# design.net
KiCad netlist of a schematic drawn in Altium Designer
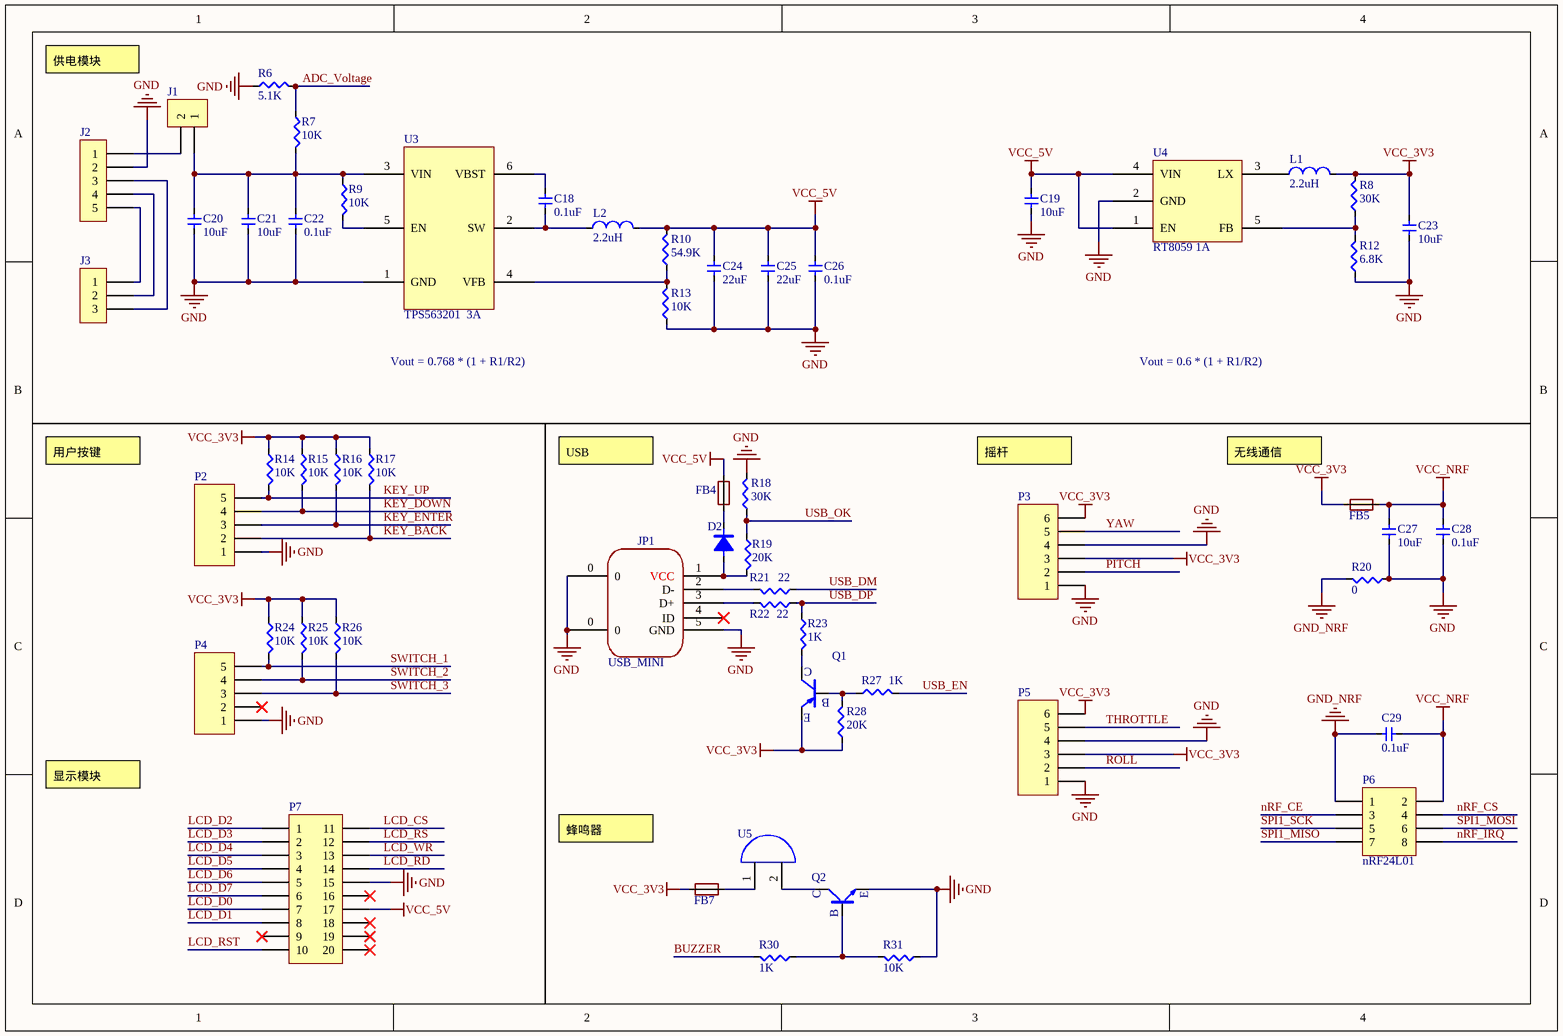
[diagram p0: 基本外设.SchDoc]

(export (version "E")
  (design (tool "Eeschema 10.0.6"))
  (components
    (comp (ref "C18")
      (value "0.1uF")
      (footprint "C 0603_L")
      (description "电容")
      (libsource (lib "SCHLIB") (part "CX_CAP"))
    )
    (comp (ref "C19")
      (value "10uF")
      (footprint "C 0603_L")
      (description "电容")
      (libsource (lib "SCHLIB") (part "CX_CAP"))
    )
    (comp (ref "C20")
      (value "10uF")
      (footprint "C 0603_L")
      (description "电容")
      (libsource (lib "SCHLIB") (part "CX_CAP"))
    )
    (comp (ref "C21")
      (value "10uF")
      (footprint "C 0603_L")
      (description "电容")
      (libsource (lib "SCHLIB") (part "CX_CAP"))
    )
    (comp (ref "C22")
      (value "0.1uF")
      (footprint "C 0603_L")
      (description "电容")
      (libsource (lib "SCHLIB") (part "CX_CAP"))
    )
    (comp (ref "C23")
      (value "10uF")
      (footprint "C 0603_L")
      (description "电容")
      (libsource (lib "SCHLIB") (part "CX_CAP"))
    )
    (comp (ref "C24")
      (value "22uF")
      (footprint "C 0603_L")
      (description "电容")
      (libsource (lib "SCHLIB") (part "CX_CAP"))
    )
    (comp (ref "C25")
      (value "22uF")
      (footprint "C 0603_L")
      (description "电容")
      (libsource (lib "SCHLIB") (part "CX_CAP"))
    )
    (comp (ref "C26")
      (value "0.1uF")
      (footprint "C 0603_L")
      (description "电容")
      (libsource (lib "SCHLIB") (part "CX_CAP"))
    )
    (comp (ref "C27")
      (value "10uF")
      (footprint "C 0603_L")
      (description "电容")
      (libsource (lib "SCHLIB") (part "CX_CAP"))
    )
    (comp (ref "C28")
      (value "0.1uF")
      (footprint "C 0603_L")
      (description "电容")
      (libsource (lib "SCHLIB") (part "CX_CAP"))
    )
    (comp (ref "C29")
      (value "0.1uF")
      (footprint "C 0603_L")
      (description "电容")
      (libsource (lib "SCHLIB") (part "CX_CAP"))
    )
    (comp (ref "D2")
      (value "DX_DIODE")
      (footprint "SMA")
      (description "普通二极管")
      (libsource (lib "MySCHLIB") (part "DX_DIODE"))
    )
    (comp (ref "FB4")
      (value "FB_BEAD")
      (footprint "FB 0603_L")
      (description "磁珠")
      (libsource (lib "MySCHLIB") (part "FB_BEAD"))
    )
    (comp (ref "FB5")
      (value "FB_BEAD")
      (footprint "FB 0603_L")
      (description "磁珠")
      (libsource (lib "") (part "FB_BEAD_1"))
    )
    (comp (ref "FB7")
      (value "FB_BEAD")
      (footprint "FB 0603_L")
      (description "磁珠")
      (libsource (lib "") (part "FB_BEAD_1"))
    )
    (comp (ref "J1")
      (value "PT_CON2")
      (footprint "PH2.0-WI-2P")
      (description "接插件")
      (libsource (lib "SCHLIB") (part "PT_CON2"))
    )
    (comp (ref "J2") (value "PT_CON5") (footprint "PH2.0-WI-5P") (libsource (lib "SCHLIB") (part "PT_CON5")))
    (comp (ref "J3") (value "~") (footprint "PH2.0-WI-3P") (libsource (lib "SCHLIB") (part "PT_CON3")))
    (comp (ref "JP1")
      (value "USB_MINI")
      (footprint "USB-MINI-5P-90度弯针")
      (libsource (lib "SCHLIB") (part "PT_USB_MINI"))
    )
    (comp (ref "L1")
      (value "2.2uH")
      (footprint "L 2520")
      (description "电感")
      (libsource (lib "SCHLIB") (part "LX_INDUCTOR_1"))
    )
    (comp (ref "L2")
      (value "2.2uH")
      (footprint "L 2520")
      (description "电感")
      (libsource (lib "SCHLIB") (part "LX_INDUCTOR_1"))
    )
    (comp (ref "P2")
      (value "Header 5")
      (footprint "XH1.25-WS-5P")
      (description "Header, 5-Pin")
      (fields (field (name "PUBLISHER") "Altium Limited"))
      (libsource (lib "Miscellaneous Connectors") (part "Header 5"))
    )
    (comp (ref "P3")
      (value "Header 6")
      (footprint "PH2.0-WS-6P")
      (description "Header, 6-Pin")
      (fields (field (name "PUBLISHER") "Altium Limited"))
      (libsource (lib "Miscellaneous Connectors") (part "Header 6"))
    )
    (comp (ref "P4")
      (value "Header 6")
      (footprint "XH1.25-WS-5P")
      (description "Header, 5-Pin")
      (fields (field (name "PUBLISHER") "Altium Limited"))
      (libsource (lib "Miscellaneous Connectors") (part "Header 5"))
    )
    (comp (ref "P5")
      (value "Header 6")
      (footprint "PH2.0-WS-6P")
      (description "Header, 6-Pin")
      (fields (field (name "PUBLISHER") "Altium Limited"))
      (libsource (lib "Miscellaneous Connectors") (part "Header 6"))
    )
    (comp (ref "P6")
      (value "nRF24L01")
      (footprint "HDR2.54-2X4")
      (description "Header, 4-Pin, Dual row")
      (fields (field (name "PUBLISHER") "Altium Limited"))
      (libsource (lib "Miscellaneous Connectors") (part "Header 4X2"))
    )
    (comp (ref "P7")
      (value "Header 10X2A")
      (footprint "LCD_2.4_TFT")
      (description "Header, 10-Pin, Dual row")
      (fields (field (name "PUBLISHER") "Altium Limited"))
      (libsource (lib "Miscellaneous Connectors") (part "Header 10X2A"))
    )
    (comp (ref "Q1")
      (value "TX_PNP")
      (footprint "SOT23-3L")
      (description "PNP三极管")
      (libsource (lib "MySCHLIB") (part "TX_PNP"))
    )
    (comp (ref "Q2")
      (value "TX_NPN")
      (footprint "SOT23-3L")
      (description "NPN三极管")
      (libsource (lib "MySCHLIB") (part "TX_NPN"))
    )
    (comp (ref "R6")
      (value "5.1K")
      (footprint "R 0603_L")
      (description "电阻")
      (libsource (lib "SCHLIB") (part "RX_RES"))
    )
    (comp (ref "R7")
      (value "10K")
      (footprint "R 0603_L")
      (description "电阻")
      (libsource (lib "SCHLIB") (part "RX_RES"))
    )
    (comp (ref "R8")
      (value "30K")
      (footprint "R 0603_L")
      (description "电阻")
      (libsource (lib "SCHLIB") (part "RX_RES"))
    )
    (comp (ref "R9")
      (value "10K")
      (footprint "R 0603_L")
      (description "电阻")
      (libsource (lib "SCHLIB") (part "RX_RES"))
    )
    (comp (ref "R10")
      (value "54.9K")
      (footprint "R 0603_L")
      (description "电阻")
      (libsource (lib "SCHLIB") (part "RX_RES"))
    )
    (comp (ref "R12")
      (value "6.8K")
      (footprint "R 0603_L")
      (description "电阻")
      (libsource (lib "SCHLIB") (part "RX_RES"))
    )
    (comp (ref "R13")
      (value "10K")
      (footprint "R 0603_L")
      (description "电阻")
      (libsource (lib "SCHLIB") (part "RX_RES"))
    )
    (comp (ref "R14")
      (value "10K")
      (footprint "R 0603_L")
      (description "电阻")
      (libsource (lib "SCHLIB") (part "RX_RES"))
    )
    (comp (ref "R15")
      (value "10K")
      (footprint "R 0603_L")
      (description "电阻")
      (libsource (lib "SCHLIB") (part "RX_RES"))
    )
    (comp (ref "R16")
      (value "10K")
      (footprint "R 0603_L")
      (description "电阻")
      (libsource (lib "SCHLIB") (part "RX_RES"))
    )
    (comp (ref "R17")
      (value "10K")
      (footprint "R 0603_L")
      (description "电阻")
      (libsource (lib "SCHLIB") (part "RX_RES"))
    )
    (comp (ref "R18")
      (value "30K")
      (footprint "R 0603_L")
      (description "电阻")
      (libsource (lib "SCHLIB") (part "RX_RES"))
    )
    (comp (ref "R19")
      (value "20K")
      (footprint "R 0603_L")
      (description "电阻")
      (libsource (lib "SCHLIB") (part "RX_RES"))
    )
    (comp (ref "R20")
      (value "0")
      (footprint "R 0603_L")
      (description "电阻")
      (libsource (lib "SCHLIB") (part "RX_RES"))
    )
    (comp (ref "R21")
      (value "22")
      (footprint "R 0603_L")
      (description "电阻")
      (libsource (lib "SCHLIB") (part "RX_RES"))
    )
    (comp (ref "R22")
      (value "22")
      (footprint "R 0603_L")
      (description "电阻")
      (libsource (lib "SCHLIB") (part "RX_RES"))
    )
    (comp (ref "R23")
      (value "1K")
      (footprint "R 0603_L")
      (description "电阻")
      (libsource (lib "SCHLIB") (part "RX_RES"))
    )
    (comp (ref "R24")
      (value "10K")
      (footprint "R 0603_L")
      (description "电阻")
      (libsource (lib "SCHLIB") (part "RX_RES"))
    )
    (comp (ref "R25")
      (value "10K")
      (footprint "R 0603_L")
      (description "电阻")
      (libsource (lib "SCHLIB") (part "RX_RES"))
    )
    (comp (ref "R26")
      (value "10K")
      (footprint "R 0603_L")
      (description "电阻")
      (libsource (lib "SCHLIB") (part "RX_RES"))
    )
    (comp (ref "R27")
      (value "1K")
      (footprint "R 0603_L")
      (description "电阻")
      (libsource (lib "SCHLIB") (part "RX_RES"))
    )
    (comp (ref "R28")
      (value "20K")
      (footprint "R 0603_L")
      (description "电阻")
      (libsource (lib "SCHLIB") (part "RX_RES"))
    )
    (comp (ref "R30")
      (value "1K")
      (footprint "R 0603_L")
      (description "电阻")
      (libsource (lib "SCHLIB") (part "RX_RES"))
    )
    (comp (ref "R31")
      (value "10K")
      (footprint "R 0603_L")
      (description "电阻")
      (libsource (lib "SCHLIB") (part "RX_RES"))
    )
    (comp (ref "U3")
      (value "TPS563201  3A")
      (footprint "SOT23-6L")
      (description "稳压电源")
      (libsource (lib "SCHLIB") (part "IC_DCDC_TPS563201"))
    )
    (comp (ref "U4")
      (value "RT8059 1A")
      (footprint "SOT23-5L")
      (description "稳压电源")
      (libsource (lib "SCHLIB") (part "IC_DCDC_RT8059"))
    )
    (comp (ref "U5")
      (value "SC_BEEP")
      (footprint "SC_Buzzer")
      (description "蜂鸣器")
      (libsource (lib "SCHLIB") (part "SC_BEEP"))
    )
  )
  (nets
    (net (code "1") (name "/ADC_Voltage") (class "Default")
      (node (ref "R6") (pin "2") (pinfunction "2_2") (pintype "passive"))
      (node (ref "R7") (pin "1") (pinfunction "1_1") (pintype "passive"))
    )
    (net (code "2") (name "/BUZZER") (class "Default")
      (node (ref "R30") (pin "2") (pinfunction "2_2") (pintype "passive"))
    )
    (net (code "3") (name "/KEY_BACK") (class "Default")
      (node (ref "P2") (pin "2") (pinfunction "2_2") (pintype "passive"))
      (node (ref "R17") (pin "2") (pinfunction "2_2") (pintype "passive"))
    )
    (net (code "4") (name "/KEY_DOWN") (class "Default")
      (node (ref "P2") (pin "4") (pinfunction "4_4") (pintype "passive"))
      (node (ref "R15") (pin "2") (pinfunction "2_2") (pintype "passive"))
    )
    (net (code "5") (name "/KEY_ENTER") (class "Default")
      (node (ref "P2") (pin "3") (pinfunction "3_3") (pintype "passive"))
      (node (ref "R16") (pin "2") (pinfunction "2_2") (pintype "passive"))
    )
    (net (code "6") (name "/KEY_UP") (class "Default")
      (node (ref "P2") (pin "5") (pinfunction "5_5") (pintype "passive"))
      (node (ref "R14") (pin "2") (pinfunction "2_2") (pintype "passive"))
    )
    (net (code "7") (name "/LCD_CS") (class "Default")
      (node (ref "P7") (pin "11") (pinfunction "11_11") (pintype "passive"))
    )
    (net (code "8") (name "/LCD_D0") (class "Default")
      (node (ref "P7") (pin "7") (pinfunction "7_7") (pintype "passive"))
    )
    (net (code "9") (name "/LCD_D1") (class "Default")
      (node (ref "P7") (pin "8") (pinfunction "8_8") (pintype "passive"))
    )
    (net (code "10") (name "/LCD_D2") (class "Default")
      (node (ref "P7") (pin "1") (pinfunction "1_1") (pintype "passive"))
    )
    (net (code "11") (name "/LCD_D3") (class "Default")
      (node (ref "P7") (pin "2") (pinfunction "2_2") (pintype "passive"))
    )
    (net (code "12") (name "/LCD_D4") (class "Default")
      (node (ref "P7") (pin "3") (pinfunction "3_3") (pintype "passive"))
    )
    (net (code "13") (name "/LCD_D5") (class "Default")
      (node (ref "P7") (pin "4") (pinfunction "4_4") (pintype "passive"))
    )
    (net (code "14") (name "/LCD_D6") (class "Default")
      (node (ref "P7") (pin "5") (pinfunction "5_5") (pintype "passive"))
    )
    (net (code "15") (name "/LCD_D7") (class "Default")
      (node (ref "P7") (pin "6") (pinfunction "6_6") (pintype "passive"))
    )
    (net (code "16") (name "/LCD_RD") (class "Default")
      (node (ref "P7") (pin "14") (pinfunction "14_14") (pintype "passive"))
    )
    (net (code "17") (name "/LCD_RS") (class "Default")
      (node (ref "P7") (pin "12") (pinfunction "12_12") (pintype "passive"))
    )
    (net (code "18") (name "/LCD_RST") (class "Default")
      (node (ref "P7") (pin "10") (pinfunction "10_10") (pintype "passive"))
    )
    (net (code "19") (name "/LCD_WR") (class "Default")
      (node (ref "P7") (pin "13") (pinfunction "13_13") (pintype "passive"))
    )
    (net (code "20") (name "/PITCH") (class "Default")
      (node (ref "P3") (pin "2") (pinfunction "2_2") (pintype "passive"))
    )
    (net (code "21") (name "/ROLL") (class "Default")
      (node (ref "P5") (pin "2") (pinfunction "2_2") (pintype "passive"))
    )
    (net (code "22") (name "/SPI1_MISO") (class "Default")
      (node (ref "P6") (pin "7") (pinfunction "7_7") (pintype "passive"))
    )
    (net (code "23") (name "/SPI1_MOSI") (class "Default")
      (node (ref "P6") (pin "6") (pinfunction "6_6") (pintype "passive"))
    )
    (net (code "24") (name "/SPI1_SCK") (class "Default")
      (node (ref "P6") (pin "5") (pinfunction "5_5") (pintype "passive"))
    )
    (net (code "25") (name "/SWITCH_1") (class "Default")
      (node (ref "P4") (pin "5") (pinfunction "5_5") (pintype "passive"))
      (node (ref "R24") (pin "2") (pinfunction "2_2") (pintype "passive"))
    )
    (net (code "26") (name "/SWITCH_2") (class "Default")
      (node (ref "P4") (pin "4") (pinfunction "4_4") (pintype "passive"))
      (node (ref "R25") (pin "2") (pinfunction "2_2") (pintype "passive"))
    )
    (net (code "27") (name "/SWITCH_3") (class "Default")
      (node (ref "P4") (pin "3") (pinfunction "3_3") (pintype "passive"))
      (node (ref "R26") (pin "2") (pinfunction "2_2") (pintype "passive"))
    )
    (net (code "28") (name "/THROTTLE") (class "Default")
      (node (ref "P5") (pin "5") (pinfunction "5_5") (pintype "passive"))
    )
    (net (code "29") (name "/USB_DM") (class "Default")
      (node (ref "R21") (pin "1") (pinfunction "1_1") (pintype "passive"))
    )
    (net (code "30") (name "/USB_DP") (class "Default")
      (node (ref "R22") (pin "1") (pinfunction "1_1") (pintype "passive"))
      (node (ref "R23") (pin "1") (pinfunction "1_1") (pintype "passive"))
    )
    (net (code "31") (name "/USB_EN") (class "Default")
      (node (ref "R27") (pin "2") (pinfunction "2_2") (pintype "passive"))
    )
    (net (code "32") (name "/USB_OK") (class "Default")
      (node (ref "R18") (pin "1") (pinfunction "1_1") (pintype "passive"))
      (node (ref "R19") (pin "1") (pinfunction "1_1") (pintype "passive"))
    )
    (net (code "33") (name "/YAW") (class "Default")
      (node (ref "P3") (pin "5") (pinfunction "5_5") (pintype "passive"))
    )
    (net (code "34") (name "/nRF_CE") (class "Default")
      (node (ref "P6") (pin "3") (pinfunction "3_3") (pintype "passive"))
    )
    (net (code "35") (name "/nRF_CS") (class "Default")
      (node (ref "P6") (pin "4") (pinfunction "4_4") (pintype "passive"))
    )
    (net (code "36") (name "/nRF_IRQ") (class "Default")
      (node (ref "P6") (pin "8") (pinfunction "8_8") (pintype "passive"))
    )
    (net (code "37") (name "GND") (class "Default")
      (node (ref "C19") (pin "2") (pinfunction "2_2") (pintype "passive"))
      (node (ref "C20") (pin "2") (pinfunction "2_2") (pintype "passive"))
      (node (ref "C21") (pin "2") (pinfunction "2_2") (pintype "passive"))
      (node (ref "C22") (pin "2") (pinfunction "2_2") (pintype "passive"))
      (node (ref "C23") (pin "2") (pinfunction "2_2") (pintype "passive"))
      (node (ref "C24") (pin "2") (pinfunction "2_2") (pintype "passive"))
      (node (ref "C25") (pin "2") (pinfunction "2_2") (pintype "passive"))
      (node (ref "C26") (pin "2") (pinfunction "2_2") (pintype "passive"))
      (node (ref "C27") (pin "2") (pinfunction "2_2") (pintype "passive"))
      (node (ref "C28") (pin "2") (pinfunction "2_2") (pintype "passive"))
      (node (ref "J2") (pin "2") (pinfunction "2_2") (pintype "passive"))
      (node (ref "JP1") (pin "0") (pinfunction "0_0") (pintype "passive"))
      (node (ref "JP1") (pin "5") (pinfunction "GND_5") (pintype "passive"))
      (node (ref "P2") (pin "1") (pinfunction "1_1") (pintype "passive"))
      (node (ref "P3") (pin "1") (pinfunction "1_1") (pintype "passive"))
      (node (ref "P3") (pin "4") (pinfunction "4_4") (pintype "passive"))
      (node (ref "P4") (pin "1") (pinfunction "1_1") (pintype "passive"))
      (node (ref "P5") (pin "1") (pinfunction "1_1") (pintype "passive"))
      (node (ref "P5") (pin "4") (pinfunction "4_4") (pintype "passive"))
      (node (ref "P7") (pin "15") (pinfunction "15_15") (pintype "passive"))
      (node (ref "Q2") (pin "2") (pinfunction "2_2") (pintype "passive"))
      (node (ref "R12") (pin "1") (pinfunction "1_1") (pintype "passive"))
      (node (ref "R13") (pin "1") (pinfunction "1_1") (pintype "passive"))
      (node (ref "R18") (pin "2") (pinfunction "2_2") (pintype "passive"))
      (node (ref "R20") (pin "1") (pinfunction "1_1") (pintype "passive"))
      (node (ref "R31") (pin "1") (pinfunction "1_1") (pintype "passive"))
      (node (ref "R6") (pin "1") (pinfunction "1_1") (pintype "passive"))
      (node (ref "U3") (pin "1") (pinfunction "GND_1") (pintype "passive"))
      (node (ref "U4") (pin "2") (pinfunction "GND_2") (pintype "passive"))
    )
    (net (code "38") (name "GND_NRF") (class "Default")
      (node (ref "C29") (pin "1") (pinfunction "1_1") (pintype "passive"))
      (node (ref "P6") (pin "1") (pinfunction "1_1") (pintype "passive"))
      (node (ref "R20") (pin "2") (pinfunction "2_2") (pintype "passive"))
    )
    (net (code "39") (name "Net-(D2-A)") (class "Default")
      (node (ref "D2") (pin "1") (pinfunction "A_1") (pintype "passive"))
      (node (ref "JP1") (pin "1") (pinfunction "VCC_1") (pintype "passive"))
      (node (ref "R19") (pin "2") (pinfunction "2_2") (pintype "passive"))
    )
    (net (code "40") (name "Net-(D2-K)") (class "Default")
      (node (ref "D2") (pin "2") (pinfunction "K_2") (pintype "passive"))
      (node (ref "FB4") (pin "1") (pinfunction "1_1") (pintype "passive"))
    )
    (net (code "41") (name "Net-(FB7-Pad1)") (class "Default")
      (node (ref "FB7") (pin "1") (pinfunction "1_1") (pintype "passive"))
      (node (ref "U5") (pin "1") (pinfunction "1_1") (pintype "passive"))
    )
    (net (code "42") (name "Net-(J1-Pad2)") (class "Default")
      (node (ref "J1") (pin "2") (pinfunction "2_2") (pintype "passive"))
      (node (ref "J2") (pin "1") (pinfunction "1_1") (pintype "passive"))
    )
    (net (code "43") (name "Net-(J2-Pad3)") (class "Default")
      (node (ref "J2") (pin "3") (pinfunction "3_3") (pintype "passive"))
      (node (ref "J3") (pin "3") (pinfunction "3_3") (pintype "passive"))
    )
    (net (code "44") (name "Net-(J2-Pad4)") (class "Default")
      (node (ref "J2") (pin "4") (pinfunction "4_4") (pintype "passive"))
      (node (ref "J3") (pin "2") (pinfunction "2_2") (pintype "passive"))
    )
    (net (code "45") (name "Net-(J2-Pad5)") (class "Default")
      (node (ref "J2") (pin "5") (pinfunction "5_5") (pintype "passive"))
      (node (ref "J3") (pin "1") (pinfunction "1_1") (pintype "passive"))
    )
    (net (code "46") (name "Net-(JP1-D+)") (class "Default")
      (node (ref "JP1") (pin "3") (pinfunction "D+_3") (pintype "passive"))
      (node (ref "R22") (pin "2") (pinfunction "2_2") (pintype "passive"))
    )
    (net (code "47") (name "Net-(JP1-D-)") (class "Default")
      (node (ref "JP1") (pin "2") (pinfunction "D-_2") (pintype "passive"))
      (node (ref "R21") (pin "2") (pinfunction "2_2") (pintype "passive"))
    )
    (net (code "48") (name "Net-(Q1-B)") (class "Default")
      (node (ref "Q1") (pin "1") (pinfunction "B_1") (pintype "passive"))
      (node (ref "R27") (pin "1") (pinfunction "1_1") (pintype "passive"))
      (node (ref "R28") (pin "2") (pinfunction "2_2") (pintype "passive"))
    )
    (net (code "49") (name "Net-(Q1-C)") (class "Default")
      (node (ref "Q1") (pin "3") (pinfunction "C_3") (pintype "passive"))
      (node (ref "R23") (pin "2") (pinfunction "2_2") (pintype "passive"))
    )
    (net (code "50") (name "Net-(Q2-Pad1)") (class "Default")
      (node (ref "Q2") (pin "1") (pinfunction "1_1") (pintype "passive"))
      (node (ref "R30") (pin "1") (pinfunction "1_1") (pintype "passive"))
      (node (ref "R31") (pin "2") (pinfunction "2_2") (pintype "passive"))
    )
    (net (code "51") (name "Net-(Q2-Pad3)") (class "Default")
      (node (ref "Q2") (pin "3") (pinfunction "3_3") (pintype "passive"))
      (node (ref "U5") (pin "2") (pinfunction "2_2") (pintype "passive"))
    )
    (net (code "52") (name "Net-(U3-EN)") (class "Default")
      (node (ref "R9") (pin "2") (pinfunction "2_2") (pintype "passive"))
      (node (ref "U3") (pin "5") (pinfunction "EN_5") (pintype "passive"))
    )
    (net (code "53") (name "Net-(U3-SW)") (class "Default")
      (node (ref "C18") (pin "2") (pinfunction "2_2") (pintype "passive"))
      (node (ref "L2") (pin "1") (pinfunction "1_1") (pintype "passive"))
      (node (ref "U3") (pin "2") (pinfunction "SW_2") (pintype "passive"))
    )
    (net (code "54") (name "Net-(U3-VBST)") (class "Default")
      (node (ref "C18") (pin "1") (pinfunction "1_1") (pintype "passive"))
      (node (ref "U3") (pin "6") (pinfunction "VBST_6") (pintype "passive"))
    )
    (net (code "55") (name "Net-(U3-VFB)") (class "Default")
      (node (ref "R10") (pin "1") (pinfunction "1_1") (pintype "passive"))
      (node (ref "R13") (pin "2") (pinfunction "2_2") (pintype "passive"))
      (node (ref "U3") (pin "4") (pinfunction "VFB_4") (pintype "passive"))
    )
    (net (code "56") (name "Net-(U3-VIN)") (class "Default")
      (node (ref "C20") (pin "1") (pinfunction "1_1") (pintype "passive"))
      (node (ref "C21") (pin "1") (pinfunction "1_1") (pintype "passive"))
      (node (ref "C22") (pin "1") (pinfunction "1_1") (pintype "passive"))
      (node (ref "J1") (pin "1") (pinfunction "1_1") (pintype "passive"))
      (node (ref "R7") (pin "2") (pinfunction "2_2") (pintype "passive"))
      (node (ref "R9") (pin "1") (pinfunction "1_1") (pintype "passive"))
      (node (ref "U3") (pin "3") (pinfunction "VIN_3") (pintype "passive"))
    )
    (net (code "57") (name "Net-(U4-FB)") (class "Default")
      (node (ref "R12") (pin "2") (pinfunction "2_2") (pintype "passive"))
      (node (ref "R8") (pin "1") (pinfunction "1_1") (pintype "passive"))
      (node (ref "U4") (pin "5") (pinfunction "FB_5") (pintype "passive"))
    )
    (net (code "58") (name "Net-(U4-LX)") (class "Default")
      (node (ref "L1") (pin "1") (pinfunction "1_1") (pintype "passive"))
      (node (ref "U4") (pin "3") (pinfunction "LX_3") (pintype "passive"))
    )
    (net (code "59") (name "VCC_3V3") (class "Default")
      (node (ref "C23") (pin "1") (pinfunction "1_1") (pintype "passive"))
      (node (ref "FB5") (pin "2") (pinfunction "2_2") (pintype "passive"))
      (node (ref "FB7") (pin "2") (pinfunction "2_2") (pintype "passive"))
      (node (ref "L1") (pin "2") (pinfunction "2_2") (pintype "passive"))
      (node (ref "P3") (pin "3") (pinfunction "3_3") (pintype "passive"))
      (node (ref "P3") (pin "6") (pinfunction "6_6") (pintype "passive"))
      (node (ref "P5") (pin "3") (pinfunction "3_3") (pintype "passive"))
      (node (ref "P5") (pin "6") (pinfunction "6_6") (pintype "passive"))
      (node (ref "Q1") (pin "2") (pinfunction "E_2") (pintype "passive"))
      (node (ref "R14") (pin "1") (pinfunction "1_1") (pintype "passive"))
      (node (ref "R15") (pin "1") (pinfunction "1_1") (pintype "passive"))
      (node (ref "R16") (pin "1") (pinfunction "1_1") (pintype "passive"))
      (node (ref "R17") (pin "1") (pinfunction "1_1") (pintype "passive"))
      (node (ref "R24") (pin "1") (pinfunction "1_1") (pintype "passive"))
      (node (ref "R25") (pin "1") (pinfunction "1_1") (pintype "passive"))
      (node (ref "R26") (pin "1") (pinfunction "1_1") (pintype "passive"))
      (node (ref "R28") (pin "1") (pinfunction "1_1") (pintype "passive"))
      (node (ref "R8") (pin "2") (pinfunction "2_2") (pintype "passive"))
    )
    (net (code "60") (name "VCC_5V") (class "Default")
      (node (ref "C19") (pin "1") (pinfunction "1_1") (pintype "passive"))
      (node (ref "C24") (pin "1") (pinfunction "1_1") (pintype "passive"))
      (node (ref "C25") (pin "1") (pinfunction "1_1") (pintype "passive"))
      (node (ref "C26") (pin "1") (pinfunction "1_1") (pintype "passive"))
      (node (ref "FB4") (pin "2") (pinfunction "2_2") (pintype "passive"))
      (node (ref "L2") (pin "2") (pinfunction "2_2") (pintype "passive"))
      (node (ref "P7") (pin "17") (pinfunction "17_17") (pintype "passive"))
      (node (ref "R10") (pin "2") (pinfunction "2_2") (pintype "passive"))
      (node (ref "U4") (pin "1") (pinfunction "EN_1") (pintype "passive"))
      (node (ref "U4") (pin "4") (pinfunction "VIN_4") (pintype "passive"))
    )
    (net (code "61") (name "VCC_NRF") (class "Default")
      (node (ref "C27") (pin "1") (pinfunction "1_1") (pintype "passive"))
      (node (ref "C28") (pin "1") (pinfunction "1_1") (pintype "passive"))
      (node (ref "C29") (pin "2") (pinfunction "2_2") (pintype "passive"))
      (node (ref "FB5") (pin "1") (pinfunction "1_1") (pintype "passive"))
      (node (ref "P6") (pin "2") (pinfunction "2_2") (pintype "passive"))
    )
    (net (code "62") (name "unconnected-(JP1-ID-Pad4)") (class "Default")
      (node (ref "JP1") (pin "4") (pinfunction "ID_4") (pintype "passive+no_connect"))
    )
    (net (code "63") (name "unconnected-(P4-Pad2)") (class "Default")
      (node (ref "P4") (pin "2") (pinfunction "2_2") (pintype "passive+no_connect"))
    )
    (net (code "64") (name "unconnected-(P7-Pad9)") (class "Default")
      (node (ref "P7") (pin "9") (pinfunction "9_9") (pintype "passive+no_connect"))
    )
    (net (code "65") (name "unconnected-(P7-Pad16)") (class "Default")
      (node (ref "P7") (pin "16") (pinfunction "16_16") (pintype "passive+no_connect"))
    )
    (net (code "66") (name "unconnected-(P7-Pad18)") (class "Default")
      (node (ref "P7") (pin "18") (pinfunction "18_18") (pintype "passive+no_connect"))
    )
    (net (code "67") (name "unconnected-(P7-Pad19)") (class "Default")
      (node (ref "P7") (pin "19") (pinfunction "19_19") (pintype "passive+no_connect"))
    )
    (net (code "68") (name "unconnected-(P7-Pad20)") (class "Default")
      (node (ref "P7") (pin "20") (pinfunction "20_20") (pintype "passive+no_connect"))
    )
  )
)
